# Sheet1.net
KiCad netlist of a schematic drawn in Altium Designer
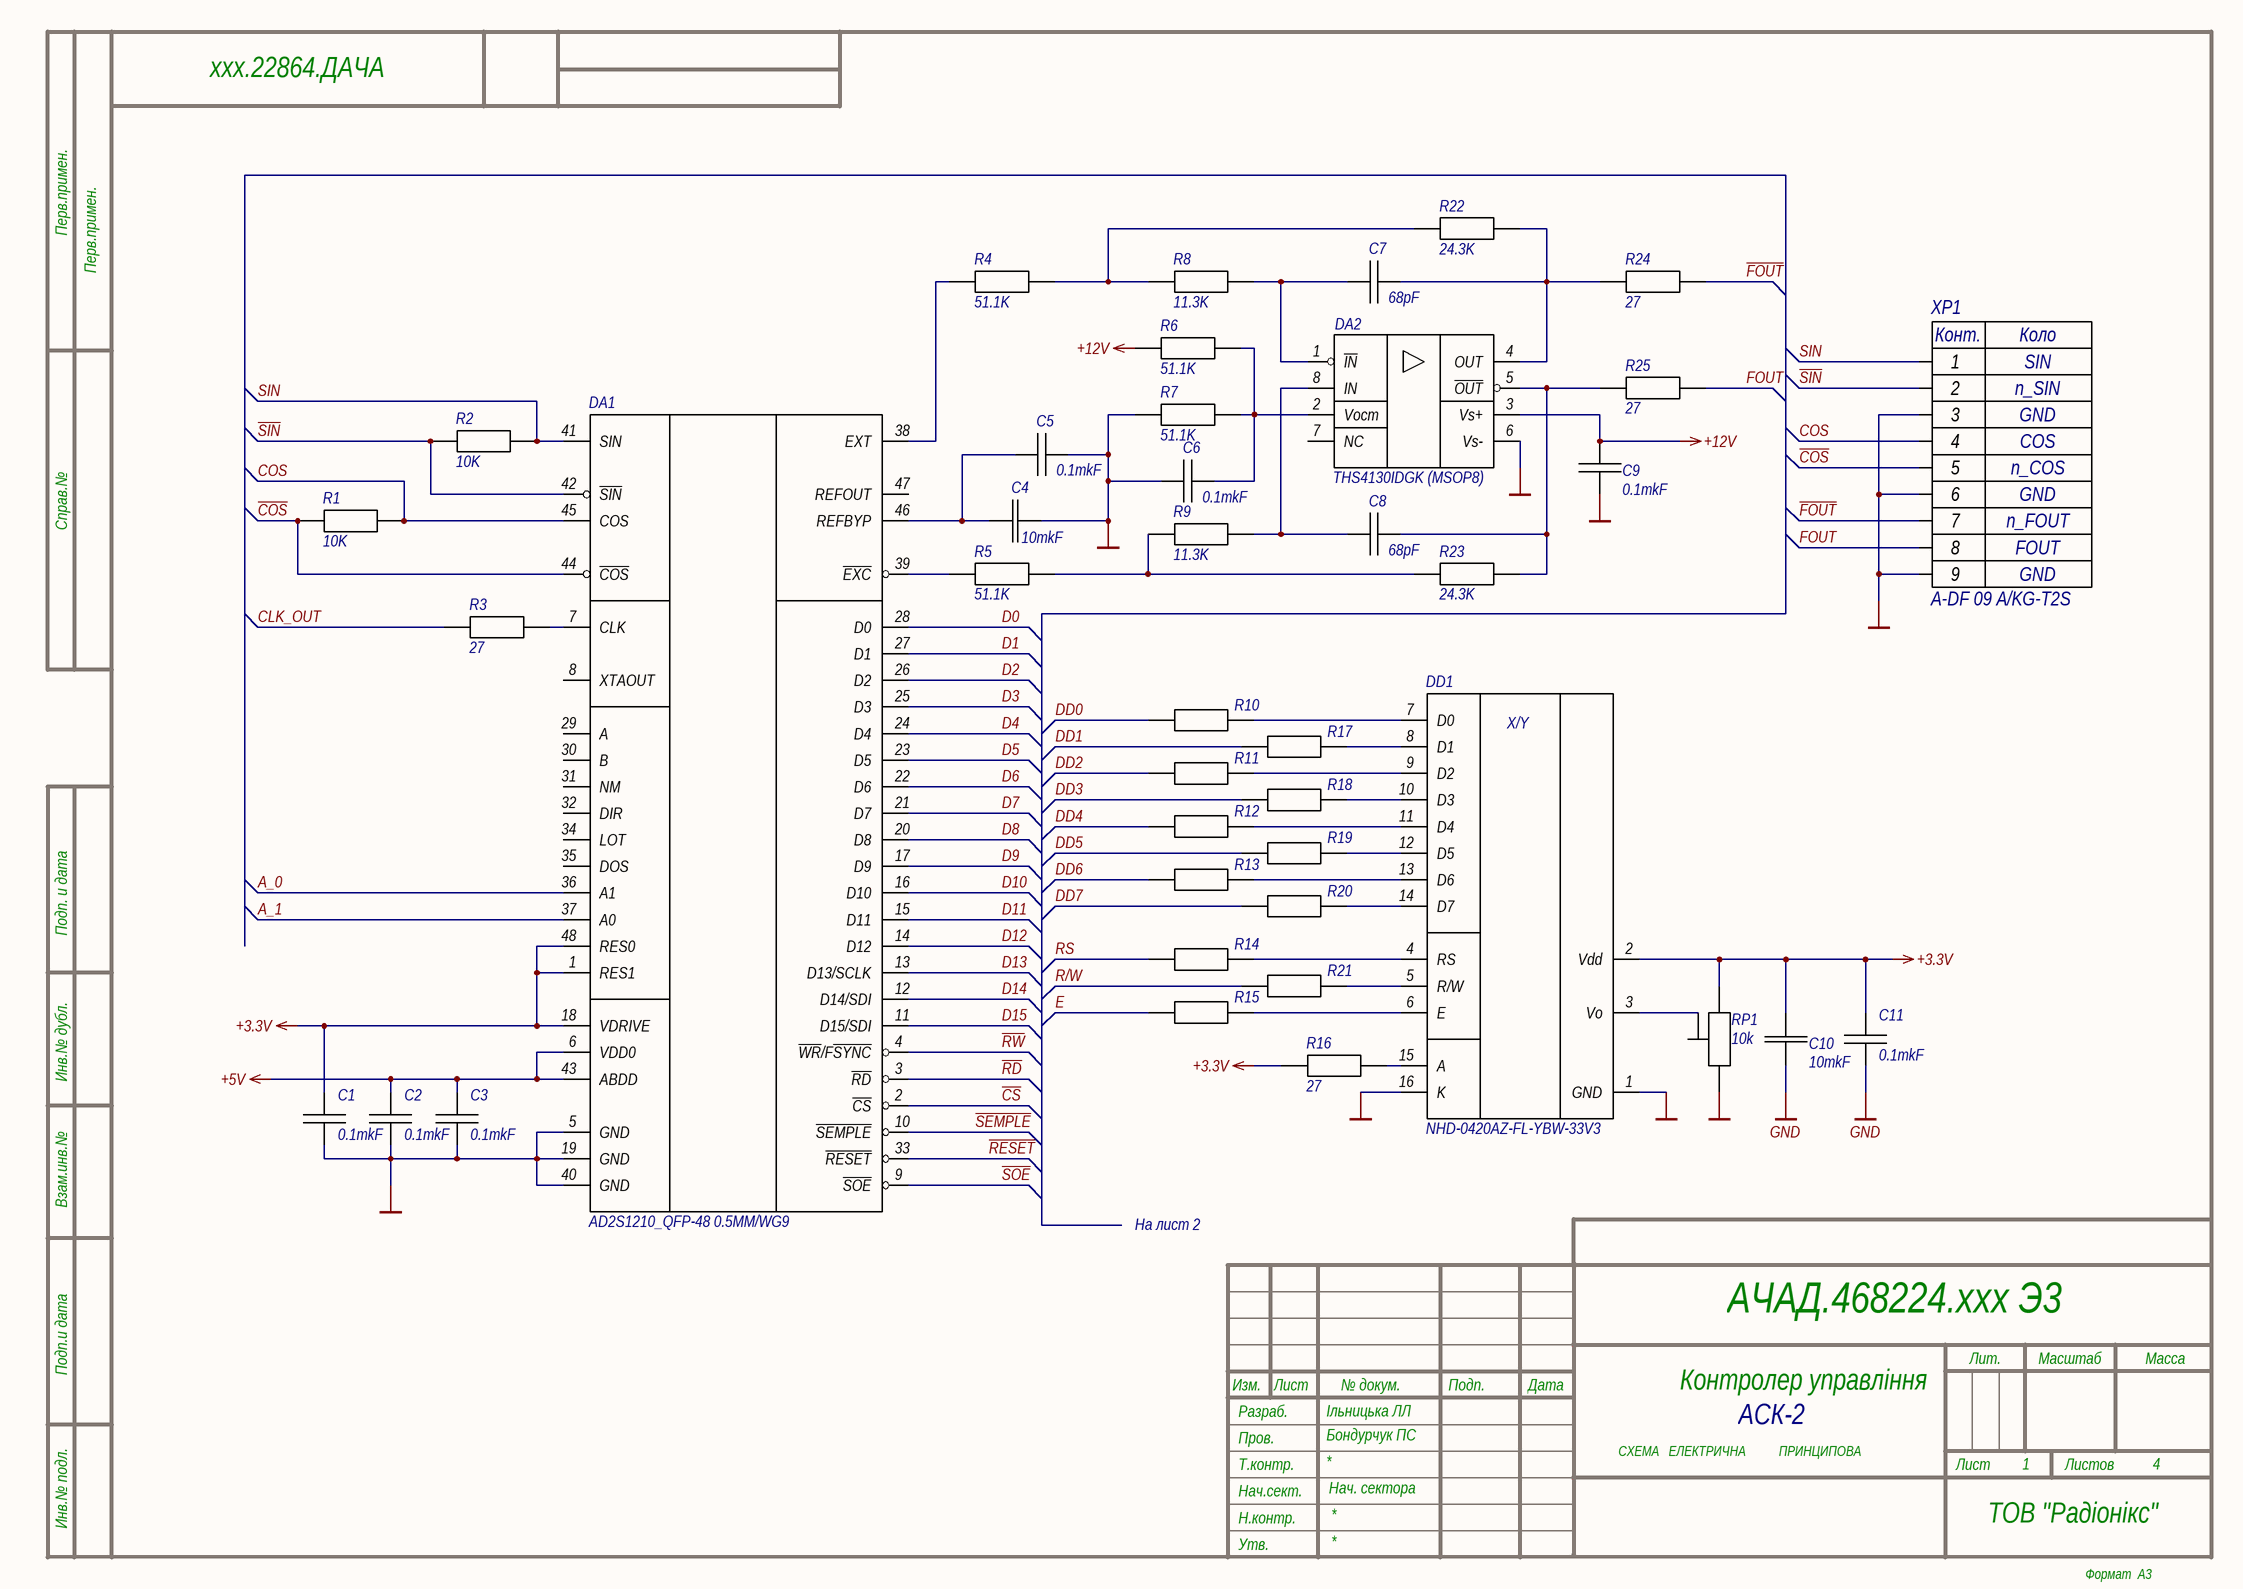
[diagram p0: Sheet1.SchDoc]

(export (version "E")
  (design (tool "Eeschema 10.0.6"))
  (components
    (comp (ref "C1")
      (value "0.1mkF")
      (footprint "C_0603")
      (description "C_0.1mkF_0603")
      (libsource (lib "АСК_1") (part "C_0.1mkF_0603"))
    )
    (comp (ref "C2")
      (value "0.1mkF")
      (footprint "C_0603")
      (description "C_0.1mkF_0603")
      (libsource (lib "АСК_1") (part "C_0.1mkF_0603"))
    )
    (comp (ref "C3")
      (value "0.1mkF")
      (footprint "C_0603")
      (description "C_0.1mkF_0603")
      (libsource (lib "АСК_1") (part "C_0.1mkF_0603"))
    )
    (comp (ref "C4")
      (value "10mkF")
      (footprint "C_1206")
      (description "C_10mkF_1206")
      (libsource (lib "АСК_1") (part "C_10mkF_1206"))
    )
    (comp (ref "C5")
      (value "0.1mkF")
      (footprint "C_0603")
      (description "C_0.1mkF_0603")
      (libsource (lib "АСК_1") (part "C_0.1mkF_0603"))
    )
    (comp (ref "C6")
      (value "0.1mkF")
      (footprint "C_0603")
      (description "C_0.1mkF_0603")
      (libsource (lib "АСК_1") (part "C_0.1mkF_0603"))
    )
    (comp (ref "C7")
      (value "68pF")
      (footprint "C_0603")
      (description "C_0.1mkF_0603")
      (libsource (lib "АСК_1") (part "C_0.1mkF_0603"))
    )
    (comp (ref "C8")
      (value "68pF")
      (footprint "C_0603")
      (description "C_0.1mkF_0603")
      (libsource (lib "АСК_1") (part "C_0.1mkF_0603"))
    )
    (comp (ref "C9")
      (value "0.1mkF")
      (footprint "C_0603")
      (description "C_0.1mkF_0603")
      (libsource (lib "АСК_1") (part "C_0.1mkF_0603"))
    )
    (comp (ref "C10")
      (value "10mkF")
      (footprint "C_1206")
      (description "C_10mkF_1206")
      (libsource (lib "АСК_1") (part "C_10mkF_1206"))
    )
    (comp (ref "C11")
      (value "0.1mkF")
      (footprint "C_0603")
      (description "C_0.1mkF_0603")
      (libsource (lib "АСК_1") (part "C_0.1mkF_0603"))
    )
    (comp (ref "DA1")
      (value "AD2S1210_QFP-48 0.5MM/WG9")
      (footprint "QFP-48 0.5MM/WG9")
      (libsource (lib "АСК_1") (part "AD2S1210_QFP-48 0.5MM/WG9"))
    )
    (comp (ref "DA2")
      (value "THS4130IDGK (MSOP8)")
      (footprint "THS4130IDGK(MSOP8)")
      (libsource (lib "АСК_1") (part "THS4130IDGK (MSOP8)"))
    )
    (comp (ref "DD1")
      (value "NHD-0420AZ-FL-YBW-33V3")
      (footprint "NHD-0420AZ-FL-YBW-33V3-ND")
      (libsource (lib "АСК_1") (part "NHD-0420AZ-FL-YBW-33V3"))
    )
    (comp (ref "R1")
      (value "10K")
      (footprint "R_0603")
      (description "R_100_0603")
      (libsource (lib "АСК_1") (part "R_100_0603"))
    )
    (comp (ref "R2")
      (value "10K")
      (footprint "R_0603")
      (description "R_100_0603")
      (libsource (lib "АСК_1") (part "R_100_0603"))
    )
    (comp (ref "R3")
      (value "27")
      (footprint "R_0603")
      (description "R_100_0603")
      (libsource (lib "АСК_1") (part "R_100_0603"))
    )
    (comp (ref "R4")
      (value "51.1K")
      (footprint "R_0603")
      (description "R_100_0603")
      (libsource (lib "АСК_1") (part "R_100_0603"))
    )
    (comp (ref "R5")
      (value "51.1K")
      (footprint "R_0603")
      (description "R_100_0603")
      (libsource (lib "АСК_1") (part "R_100_0603"))
    )
    (comp (ref "R6")
      (value "51.1K")
      (footprint "R_0603")
      (description "R_100_0603")
      (libsource (lib "АСК_1") (part "R_100_0603"))
    )
    (comp (ref "R7")
      (value "51.1K")
      (footprint "R_0603")
      (description "R_100_0603")
      (libsource (lib "АСК_1") (part "R_100_0603"))
    )
    (comp (ref "R8")
      (value "11.3K")
      (footprint "R_0603")
      (description "R_100_0603")
      (libsource (lib "АСК_1") (part "R_100_0603"))
    )
    (comp (ref "R9")
      (value "11.3K")
      (footprint "R_0603")
      (description "R_100_0603")
      (libsource (lib "АСК_1") (part "R_100_0603"))
    )
    (comp (ref "R10")
      (value "27")
      (footprint "R_0603")
      (description "R_100_0603")
      (libsource (lib "АСК_1") (part "R_100_0603"))
    )
    (comp (ref "R11")
      (value "27")
      (footprint "R_0603")
      (description "R_100_0603")
      (libsource (lib "АСК_1") (part "R_100_0603"))
    )
    (comp (ref "R12")
      (value "27")
      (footprint "R_0603")
      (description "R_100_0603")
      (libsource (lib "АСК_1") (part "R_100_0603"))
    )
    (comp (ref "R13")
      (value "27")
      (footprint "R_0603")
      (description "R_100_0603")
      (libsource (lib "АСК_1") (part "R_100_0603"))
    )
    (comp (ref "R14")
      (value "27")
      (footprint "R_0603")
      (description "R_100_0603")
      (libsource (lib "АСК_1") (part "R_100_0603"))
    )
    (comp (ref "R15")
      (value "27")
      (footprint "R_0603")
      (description "R_100_0603")
      (libsource (lib "АСК_1") (part "R_100_0603"))
    )
    (comp (ref "R16")
      (value "27")
      (footprint "R_1206")
      (description "R_10_1206")
      (libsource (lib "АСК_1") (part "R_10_1206"))
    )
    (comp (ref "R17")
      (value "27")
      (footprint "R_0603")
      (description "R_100_0603")
      (libsource (lib "АСК_1") (part "R_100_0603"))
    )
    (comp (ref "R18")
      (value "27")
      (footprint "R_0603")
      (description "R_100_0603")
      (libsource (lib "АСК_1") (part "R_100_0603"))
    )
    (comp (ref "R19")
      (value "27")
      (footprint "R_0603")
      (description "R_100_0603")
      (libsource (lib "АСК_1") (part "R_100_0603"))
    )
    (comp (ref "R20")
      (value "27")
      (footprint "R_0603")
      (description "R_100_0603")
      (libsource (lib "АСК_1") (part "R_100_0603"))
    )
    (comp (ref "R21")
      (value "27")
      (footprint "R_0603")
      (description "R_100_0603")
      (libsource (lib "АСК_1") (part "R_100_0603"))
    )
    (comp (ref "R22")
      (value "24.3K")
      (footprint "R_0603")
      (description "R_100_0603")
      (libsource (lib "АСК_1") (part "R_100_0603"))
    )
    (comp (ref "R23")
      (value "24.3K")
      (footprint "R_0603")
      (description "R_100_0603")
      (libsource (lib "АСК_1") (part "R_100_0603"))
    )
    (comp (ref "R24")
      (value "27")
      (footprint "R_0603")
      (description "R_100_0603")
      (libsource (lib "АСК_1") (part "R_100_0603"))
    )
    (comp (ref "R25")
      (value "27")
      (footprint "R_0603")
      (description "R_100_0603")
      (libsource (lib "АСК_1") (part "R_100_0603"))
    )
    (comp (ref "RP1")
      (value "10k")
      (footprint "RES_TRIMMER_3361P-1-103GLF")
      (description "R_10k_RES_TRIMMER_3361P-1-103GLF")
      (libsource (lib "АСК_1") (part "R_10k_RES_TRIMMER"))
    )
    (comp (ref "XP1") (value "A-DF 09 A/KG-T2S") (libsource (lib "АСК_1") (part "A-DF 09 A/KG-T2S")))
  )
  (nets
    (net (code "1") (name "+3.3V") (class "Default")
      (node (ref "C1") (pin "2") (pinfunction "2_2") (pintype "passive"))
      (node (ref "C10") (pin "2") (pinfunction "2_2") (pintype "passive"))
      (node (ref "C11") (pin "2") (pinfunction "2_2") (pintype "passive"))
      (node (ref "DA1") (pin "1") (pinfunction "RES1_1") (pintype "passive"))
      (node (ref "DA1") (pin "18") (pinfunction "VDRIVE_18") (pintype "passive"))
      (node (ref "DA1") (pin "48") (pinfunction "RES0_48") (pintype "passive"))
      (node (ref "DD1") (pin "2") (pinfunction "Vdd_2") (pintype "passive"))
      (node (ref "R16") (pin "1") (pinfunction "1_1") (pintype "passive"))
      (node (ref "RP1") (pin "2") (pinfunction "2_2") (pintype "passive"))
    )
    (net (code "2") (name "+5V") (class "Default")
      (node (ref "C2") (pin "2") (pinfunction "2_2") (pintype "passive"))
      (node (ref "C3") (pin "2") (pinfunction "2_2") (pintype "passive"))
      (node (ref "DA1") (pin "43") (pinfunction "ABDD_43") (pintype "passive"))
      (node (ref "DA1") (pin "6") (pinfunction "VDD0_6") (pintype "passive"))
    )
    (net (code "3") (name "+12V") (class "Default")
      (node (ref "C9") (pin "1") (pinfunction "1_1") (pintype "passive"))
      (node (ref "DA2") (pin "3") (pinfunction "Vs+_3") (pintype "passive"))
      (node (ref "R6") (pin "1") (pinfunction "1_1") (pintype "passive"))
    )
    (net (code "4") (name "/A_0") (class "Default")
      (node (ref "DA1") (pin "36") (pinfunction "A1_36") (pintype "passive"))
    )
    (net (code "5") (name "/A_1") (class "Default")
      (node (ref "DA1") (pin "37") (pinfunction "A0_37") (pintype "passive"))
    )
    (net (code "6") (name "/CLK_OUT") (class "Default")
      (node (ref "R3") (pin "1") (pinfunction "1_1") (pintype "passive"))
    )
    (net (code "7") (name "/COS") (class "Default")
      (node (ref "DA1") (pin "45") (pinfunction "COS_45") (pintype "passive"))
      (node (ref "R1") (pin "1") (pinfunction "1_1") (pintype "passive"))
      (node (ref "XP1") (pin "4") (pinfunction "4_4") (pintype "passive"))
    )
    (net (code "8") (name "/D0") (class "Default")
      (node (ref "DA1") (pin "28") (pinfunction "D0_28") (pintype "passive"))
    )
    (net (code "9") (name "/D1") (class "Default")
      (node (ref "DA1") (pin "27") (pinfunction "D1_27") (pintype "passive"))
    )
    (net (code "10") (name "/D2") (class "Default")
      (node (ref "DA1") (pin "26") (pinfunction "D2_26") (pintype "passive"))
    )
    (net (code "11") (name "/D3") (class "Default")
      (node (ref "DA1") (pin "25") (pinfunction "D3_25") (pintype "passive"))
    )
    (net (code "12") (name "/D4") (class "Default")
      (node (ref "DA1") (pin "24") (pinfunction "D4_24") (pintype "passive"))
    )
    (net (code "13") (name "/D5") (class "Default")
      (node (ref "DA1") (pin "23") (pinfunction "D5_23") (pintype "passive"))
    )
    (net (code "14") (name "/D6") (class "Default")
      (node (ref "DA1") (pin "22") (pinfunction "D6_22") (pintype "passive"))
    )
    (net (code "15") (name "/D7") (class "Default")
      (node (ref "DA1") (pin "21") (pinfunction "D7_21") (pintype "passive"))
    )
    (net (code "16") (name "/D8") (class "Default")
      (node (ref "DA1") (pin "20") (pinfunction "D8_20") (pintype "passive"))
    )
    (net (code "17") (name "/D9") (class "Default")
      (node (ref "DA1") (pin "17") (pinfunction "D9_17") (pintype "passive"))
    )
    (net (code "18") (name "/D10") (class "Default")
      (node (ref "DA1") (pin "16") (pinfunction "D10_16") (pintype "passive"))
    )
    (net (code "19") (name "/D11") (class "Default")
      (node (ref "DA1") (pin "15") (pinfunction "D11_15") (pintype "passive"))
    )
    (net (code "20") (name "/D12") (class "Default")
      (node (ref "DA1") (pin "14") (pinfunction "D12_14") (pintype "passive"))
    )
    (net (code "21") (name "/D13") (class "Default")
      (node (ref "DA1") (pin "13") (pinfunction "D13/SCLK_13") (pintype "passive"))
    )
    (net (code "22") (name "/D14") (class "Default")
      (node (ref "DA1") (pin "12") (pinfunction "D14/SDI_12") (pintype "passive"))
    )
    (net (code "23") (name "/D15") (class "Default")
      (node (ref "DA1") (pin "11") (pinfunction "D15/SDI_11") (pintype "passive"))
    )
    (net (code "24") (name "/DD0") (class "Default")
      (node (ref "R10") (pin "1") (pinfunction "1_1") (pintype "passive"))
    )
    (net (code "25") (name "/DD1") (class "Default")
      (node (ref "R17") (pin "1") (pinfunction "1_1") (pintype "passive"))
    )
    (net (code "26") (name "/DD2") (class "Default")
      (node (ref "R11") (pin "1") (pinfunction "1_1") (pintype "passive"))
    )
    (net (code "27") (name "/DD3") (class "Default")
      (node (ref "R18") (pin "1") (pinfunction "1_1") (pintype "passive"))
    )
    (net (code "28") (name "/DD4") (class "Default")
      (node (ref "R12") (pin "1") (pinfunction "1_1") (pintype "passive"))
    )
    (net (code "29") (name "/DD5") (class "Default")
      (node (ref "R19") (pin "1") (pinfunction "1_1") (pintype "passive"))
    )
    (net (code "30") (name "/DD6") (class "Default")
      (node (ref "R13") (pin "1") (pinfunction "1_1") (pintype "passive"))
    )
    (net (code "31") (name "/DD7") (class "Default")
      (node (ref "R20") (pin "1") (pinfunction "1_1") (pintype "passive"))
    )
    (net (code "32") (name "/E") (class "Default")
      (node (ref "R15") (pin "1") (pinfunction "1_1") (pintype "passive"))
    )
    (net (code "33") (name "/FOUT") (class "Default")
      (node (ref "R25") (pin "2") (pinfunction "2_2") (pintype "passive"))
      (node (ref "XP1") (pin "8") (pinfunction "8_8") (pintype "passive"))
    )
    (net (code "34") (name "/RS") (class "Default")
      (node (ref "R14") (pin "1") (pinfunction "1_1") (pintype "passive"))
    )
    (net (code "35") (name "/R{slash}W") (class "Default")
      (node (ref "R21") (pin "1") (pinfunction "1_1") (pintype "passive"))
    )
    (net (code "36") (name "/SIN") (class "Default")
      (node (ref "DA1") (pin "41") (pinfunction "SIN_41") (pintype "passive"))
      (node (ref "R2") (pin "2") (pinfunction "2_2") (pintype "passive"))
      (node (ref "XP1") (pin "1") (pinfunction "1_1") (pintype "passive"))
    )
    (net (code "37") (name "/~{COS}") (class "Default")
      (node (ref "DA1") (pin "44") (pinfunction "~{COS}_44") (pintype "passive"))
      (node (ref "R1") (pin "2") (pinfunction "2_2") (pintype "passive"))
      (node (ref "XP1") (pin "5") (pinfunction "5_5") (pintype "passive"))
    )
    (net (code "38") (name "/~{CS}") (class "Default")
      (node (ref "DA1") (pin "2") (pinfunction "~{CS}_2") (pintype "passive"))
    )
    (net (code "39") (name "/~{FOUT}") (class "Default")
      (node (ref "R24") (pin "2") (pinfunction "2_2") (pintype "passive"))
      (node (ref "XP1") (pin "7") (pinfunction "7_7") (pintype "passive"))
    )
    (net (code "40") (name "/~{RD}") (class "Default")
      (node (ref "DA1") (pin "3") (pinfunction "~{RD}_3") (pintype "passive"))
    )
    (net (code "41") (name "/~{RESET}") (class "Default")
      (node (ref "DA1") (pin "33") (pinfunction "~{RESET}_33") (pintype "passive"))
    )
    (net (code "42") (name "/~{RW}") (class "Default")
      (node (ref "DA1") (pin "4") (pinfunction "~{WR}/F~{SYNC}_4") (pintype "passive"))
    )
    (net (code "43") (name "/~{SEMPLE}") (class "Default")
      (node (ref "DA1") (pin "10") (pinfunction "~{SEMPLE}_10") (pintype "passive"))
    )
    (net (code "44") (name "/~{SIN}") (class "Default")
      (node (ref "DA1") (pin "42") (pinfunction "~{SIN}_42") (pintype "passive"))
      (node (ref "R2") (pin "1") (pinfunction "1_1") (pintype "passive"))
      (node (ref "XP1") (pin "2") (pinfunction "2_2") (pintype "passive"))
    )
    (net (code "45") (name "/~{SOE}") (class "Default")
      (node (ref "DA1") (pin "9") (pinfunction "~{SOE}_9") (pintype "passive"))
    )
    (net (code "46") (name "GND") (class "Default")
      (node (ref "C1") (pin "1") (pinfunction "1_1") (pintype "passive"))
      (node (ref "C10") (pin "1") (pinfunction "1_1") (pintype "passive"))
      (node (ref "C11") (pin "1") (pinfunction "1_1") (pintype "passive"))
      (node (ref "C2") (pin "1") (pinfunction "1_1") (pintype "passive"))
      (node (ref "C3") (pin "1") (pinfunction "1_1") (pintype "passive"))
      (node (ref "C4") (pin "2") (pinfunction "2_2") (pintype "passive"))
      (node (ref "C5") (pin "1") (pinfunction "1_1") (pintype "passive"))
      (node (ref "C6") (pin "2") (pinfunction "2_2") (pintype "passive"))
      (node (ref "C9") (pin "2") (pinfunction "2_2") (pintype "passive"))
      (node (ref "DA1") (pin "19") (pinfunction "GND_19") (pintype "passive"))
      (node (ref "DA1") (pin "40") (pinfunction "GND_40") (pintype "passive"))
      (node (ref "DA1") (pin "5") (pinfunction "GND_5") (pintype "passive"))
      (node (ref "DA2") (pin "6") (pinfunction "Vs-_6") (pintype "passive"))
      (node (ref "DD1") (pin "1") (pinfunction "GND_1") (pintype "passive"))
      (node (ref "DD1") (pin "16") (pinfunction "K_16") (pintype "passive"))
      (node (ref "R7") (pin "1") (pinfunction "1_1") (pintype "passive"))
      (node (ref "RP1") (pin "1") (pinfunction "1_1") (pintype "passive"))
      (node (ref "XP1") (pin "3") (pinfunction "3_3") (pintype "passive"))
      (node (ref "XP1") (pin "6") (pinfunction "6_6") (pintype "passive"))
      (node (ref "XP1") (pin "9") (pinfunction "9_9") (pintype "passive"))
    )
    (net (code "47") (name "Net-(DA1-CLK)") (class "Default")
      (node (ref "DA1") (pin "7") (pinfunction "CLK_7") (pintype "passive"))
      (node (ref "R3") (pin "2") (pinfunction "2_2") (pintype "passive"))
    )
    (net (code "48") (name "Net-(DA1-EXT)") (class "Default")
      (node (ref "DA1") (pin "38") (pinfunction "EXT_38") (pintype "passive"))
      (node (ref "R4") (pin "1") (pinfunction "1_1") (pintype "passive"))
    )
    (net (code "49") (name "Net-(DA1-REFBYP)") (class "Default")
      (node (ref "C4") (pin "1") (pinfunction "1_1") (pintype "passive"))
      (node (ref "C5") (pin "2") (pinfunction "2_2") (pintype "passive"))
      (node (ref "DA1") (pin "46") (pinfunction "REFBYP_46") (pintype "passive"))
    )
    (net (code "50") (name "Net-(DA1-~{EXC})") (class "Default")
      (node (ref "DA1") (pin "39") (pinfunction "~{EXC}_39") (pintype "passive"))
      (node (ref "R5") (pin "1") (pinfunction "1_1") (pintype "passive"))
    )
    (net (code "51") (name "Net-(DA2-IN)") (class "Default")
      (node (ref "C8") (pin "2") (pinfunction "2_2") (pintype "passive"))
      (node (ref "DA2") (pin "8") (pinfunction "IN_8") (pintype "passive"))
      (node (ref "R9") (pin "2") (pinfunction "2_2") (pintype "passive"))
    )
    (net (code "52") (name "Net-(DA2-OUT)") (class "Default")
      (node (ref "C7") (pin "1") (pinfunction "1_1") (pintype "passive"))
      (node (ref "DA2") (pin "4") (pinfunction "OUT_4") (pintype "passive"))
      (node (ref "R22") (pin "2") (pinfunction "2_2") (pintype "passive"))
      (node (ref "R24") (pin "1") (pinfunction "1_1") (pintype "passive"))
    )
    (net (code "53") (name "Net-(DA2-Vocm)") (class "Default")
      (node (ref "C6") (pin "1") (pinfunction "1_1") (pintype "passive"))
      (node (ref "DA2") (pin "2") (pinfunction "Vocm_2") (pintype "passive"))
      (node (ref "R6") (pin "2") (pinfunction "2_2") (pintype "passive"))
      (node (ref "R7") (pin "2") (pinfunction "2_2") (pintype "passive"))
    )
    (net (code "54") (name "Net-(DA2-~{IN})") (class "Default")
      (node (ref "C7") (pin "2") (pinfunction "2_2") (pintype "passive"))
      (node (ref "DA2") (pin "1") (pinfunction "~{IN}_1") (pintype "passive"))
      (node (ref "R8") (pin "2") (pinfunction "2_2") (pintype "passive"))
    )
    (net (code "55") (name "Net-(DA2-~{OUT})") (class "Default")
      (node (ref "C8") (pin "1") (pinfunction "1_1") (pintype "passive"))
      (node (ref "DA2") (pin "5") (pinfunction "~{OUT}_5") (pintype "passive"))
      (node (ref "R23") (pin "1") (pinfunction "1_1") (pintype "passive"))
      (node (ref "R25") (pin "1") (pinfunction "1_1") (pintype "passive"))
    )
    (net (code "56") (name "Net-(DD1-A)") (class "Default")
      (node (ref "DD1") (pin "15") (pinfunction "A_15") (pintype "passive"))
      (node (ref "R16") (pin "2") (pinfunction "2_2") (pintype "passive"))
    )
    (net (code "57") (name "Net-(DD1-D0)") (class "Default")
      (node (ref "DD1") (pin "7") (pinfunction "D0_7") (pintype "passive"))
      (node (ref "R10") (pin "2") (pinfunction "2_2") (pintype "passive"))
    )
    (net (code "58") (name "Net-(DD1-D1)") (class "Default")
      (node (ref "DD1") (pin "8") (pinfunction "D1_8") (pintype "passive"))
      (node (ref "R17") (pin "2") (pinfunction "2_2") (pintype "passive"))
    )
    (net (code "59") (name "Net-(DD1-D2)") (class "Default")
      (node (ref "DD1") (pin "9") (pinfunction "D2_9") (pintype "passive"))
      (node (ref "R11") (pin "2") (pinfunction "2_2") (pintype "passive"))
    )
    (net (code "60") (name "Net-(DD1-D3)") (class "Default")
      (node (ref "DD1") (pin "10") (pinfunction "D3_10") (pintype "passive"))
      (node (ref "R18") (pin "2") (pinfunction "2_2") (pintype "passive"))
    )
    (net (code "61") (name "Net-(DD1-D4)") (class "Default")
      (node (ref "DD1") (pin "11") (pinfunction "D4_11") (pintype "passive"))
      (node (ref "R12") (pin "2") (pinfunction "2_2") (pintype "passive"))
    )
    (net (code "62") (name "Net-(DD1-D5)") (class "Default")
      (node (ref "DD1") (pin "12") (pinfunction "D5_12") (pintype "passive"))
      (node (ref "R19") (pin "2") (pinfunction "2_2") (pintype "passive"))
    )
    (net (code "63") (name "Net-(DD1-D6)") (class "Default")
      (node (ref "DD1") (pin "13") (pinfunction "D6_13") (pintype "passive"))
      (node (ref "R13") (pin "2") (pinfunction "2_2") (pintype "passive"))
    )
    (net (code "64") (name "Net-(DD1-D7)") (class "Default")
      (node (ref "DD1") (pin "14") (pinfunction "D7_14") (pintype "passive"))
      (node (ref "R20") (pin "2") (pinfunction "2_2") (pintype "passive"))
    )
    (net (code "65") (name "Net-(DD1-E)") (class "Default")
      (node (ref "DD1") (pin "6") (pinfunction "E_6") (pintype "passive"))
      (node (ref "R15") (pin "2") (pinfunction "2_2") (pintype "passive"))
    )
    (net (code "66") (name "Net-(DD1-RS)") (class "Default")
      (node (ref "DD1") (pin "4") (pinfunction "RS_4") (pintype "passive"))
      (node (ref "R14") (pin "2") (pinfunction "2_2") (pintype "passive"))
    )
    (net (code "67") (name "Net-(DD1-R{slash}W)") (class "Default")
      (node (ref "DD1") (pin "5") (pinfunction "R/W_5") (pintype "passive"))
      (node (ref "R21") (pin "2") (pinfunction "2_2") (pintype "passive"))
    )
    (net (code "68") (name "Net-(DD1-Vo)") (class "Default")
      (node (ref "DD1") (pin "3") (pinfunction "Vo_3") (pintype "passive"))
      (node (ref "RP1") (pin "3") (pinfunction "3_3") (pintype "passive"))
    )
    (net (code "69") (name "Net-(R22-Pad1)") (class "Default")
      (node (ref "R22") (pin "1") (pinfunction "1_1") (pintype "passive"))
      (node (ref "R4") (pin "2") (pinfunction "2_2") (pintype "passive"))
      (node (ref "R8") (pin "1") (pinfunction "1_1") (pintype "passive"))
    )
    (net (code "70") (name "Net-(R23-Pad2)") (class "Default")
      (node (ref "R23") (pin "2") (pinfunction "2_2") (pintype "passive"))
      (node (ref "R5") (pin "2") (pinfunction "2_2") (pintype "passive"))
      (node (ref "R9") (pin "1") (pinfunction "1_1") (pintype "passive"))
    )
    (net (code "71") (name "unconnected-(DA1-A-Pad29)") (class "Default")
      (node (ref "DA1") (pin "29") (pinfunction "A_29") (pintype "passive"))
    )
    (net (code "72") (name "unconnected-(DA1-B-Pad30)") (class "Default")
      (node (ref "DA1") (pin "30") (pinfunction "B_30") (pintype "passive"))
    )
    (net (code "73") (name "unconnected-(DA1-DIR-Pad32)") (class "Default")
      (node (ref "DA1") (pin "32") (pinfunction "DIR_32") (pintype "passive"))
    )
    (net (code "74") (name "unconnected-(DA1-DOS-Pad35)") (class "Default")
      (node (ref "DA1") (pin "35") (pinfunction "DOS_35") (pintype "passive"))
    )
    (net (code "75") (name "unconnected-(DA1-LOT-Pad34)") (class "Default")
      (node (ref "DA1") (pin "34") (pinfunction "LOT_34") (pintype "passive"))
    )
    (net (code "76") (name "unconnected-(DA1-NM-Pad31)") (class "Default")
      (node (ref "DA1") (pin "31") (pinfunction "NM_31") (pintype "passive"))
    )
    (net (code "77") (name "unconnected-(DA1-REFOUT-Pad47)") (class "Default")
      (node (ref "DA1") (pin "47") (pinfunction "REFOUT_47") (pintype "passive"))
    )
    (net (code "78") (name "unconnected-(DA1-XTAOUT-Pad8)") (class "Default")
      (node (ref "DA1") (pin "8") (pinfunction "XTAOUT_8") (pintype "passive"))
    )
    (net (code "79") (name "unconnected-(DA2-NC-Pad7)") (class "Default")
      (node (ref "DA2") (pin "7") (pinfunction "NC_7") (pintype "passive"))
    )
  )
)
